# wiPOWER.net
KiCad netlist of a schematic drawn in EAGLE
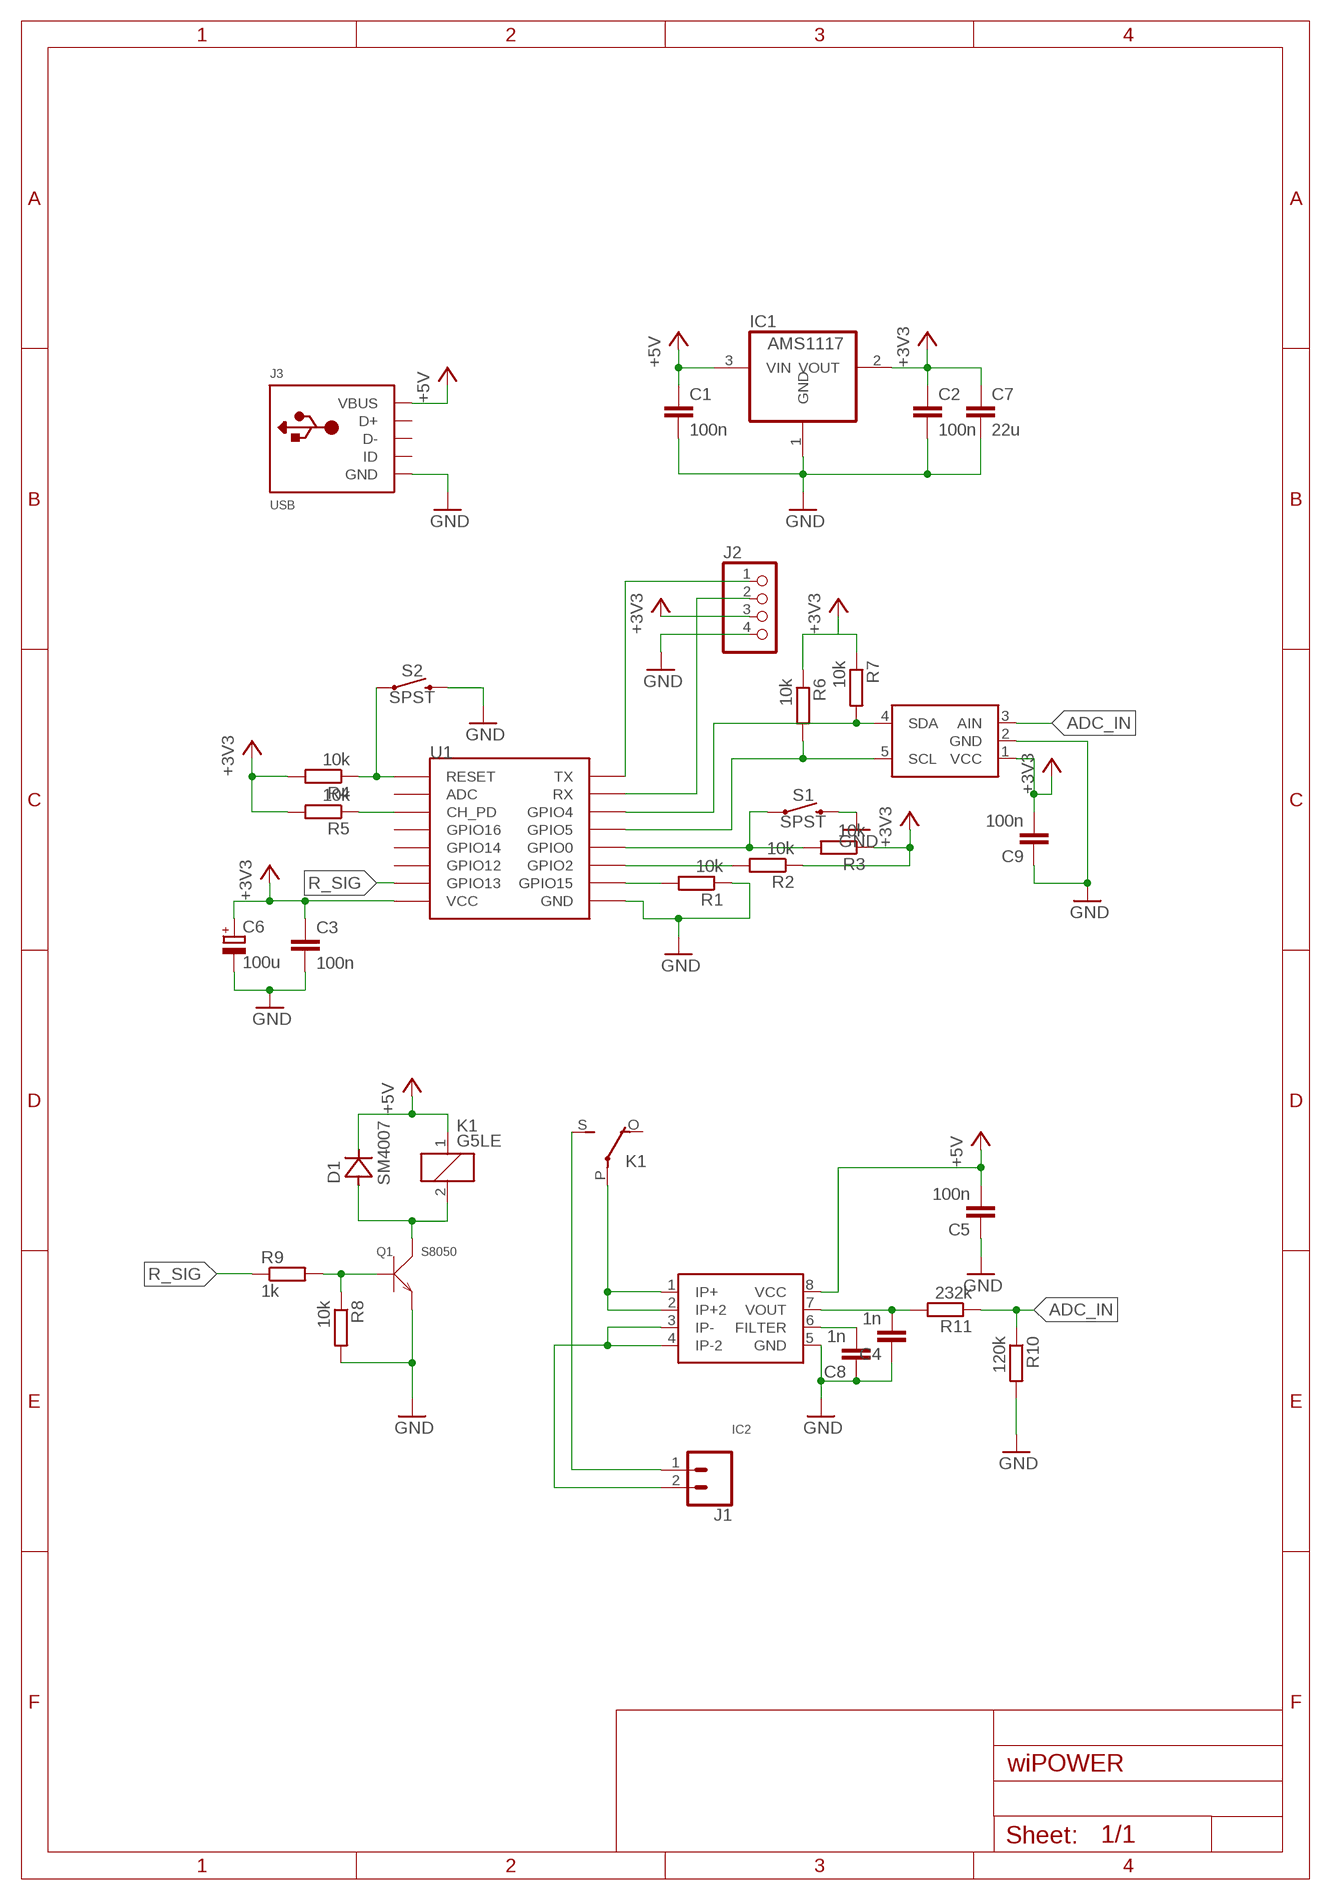
[diagram p0: schematic, sheet 1]

(export (version "E")
  (design (tool "Eeschema 10.0.6"))
  (components
    (comp (ref "C1")
      (value "100n")
      (footprint "eagle-import:C0603")
      (libsource (lib "eagle-import") (part "C-EUC0603"))
    )
    (comp (ref "C2")
      (value "100n")
      (footprint "eagle-import:C0603")
      (libsource (lib "eagle-import") (part "C-EUC0603"))
    )
    (comp (ref "C3")
      (value "100n")
      (footprint "eagle-import:C0603")
      (libsource (lib "eagle-import") (part "C-EUC0603"))
    )
    (comp (ref "C4")
      (value "1n")
      (footprint "eagle-import:C0603")
      (libsource (lib "eagle-import") (part "C-EUC0603"))
    )
    (comp (ref "C5")
      (value "100n")
      (footprint "eagle-import:C0603")
      (libsource (lib "eagle-import") (part "C-EUC0603"))
    )
    (comp (ref "C6")
      (value "100u")
      (footprint "eagle-import:B_3528-21R")
      (libsource (lib "eagle-import") (part "CPOL-EUB/3528-21R"))
    )
    (comp (ref "C7")
      (value "22u")
      (footprint "eagle-import:C0603")
      (libsource (lib "eagle-import") (part "C-EUC0603"))
    )
    (comp (ref "C8")
      (value "1n")
      (footprint "eagle-import:C0603")
      (libsource (lib "eagle-import") (part "C-EUC0603"))
    )
    (comp (ref "C9")
      (value "100n")
      (footprint "eagle-import:C0603")
      (libsource (lib "eagle-import") (part "C-EUC0603"))
    )
    (comp (ref "D1")
      (value "SM4007")
      (footprint "eagle-import:DIODE_SOD123")
      (libsource (lib "eagle-import") (part "SM4007PL"))
    )
    (comp (ref "IC1")
      (value "AMS1117")
      (footprint "eagle-import:SOT223")
      (fields (field (name "MPN") "REG1117"))
      (libsource (lib "eagle-import") (part "REG1117"))
    )
    (comp (ref "IC2")
      (value "ACS724")
      (footprint "eagle-import:SOIC8")
      (libsource (lib "eagle-import") (part "ACS724"))
    )
    (comp (ref "J1")
      (value "CONN_025MM")
      (footprint "eagle-import:SCREWTERMINAL-5MM-2")
      (libsource (lib "eagle-import") (part "CONN_025MM"))
    )
    (comp (ref "J2")
      (value "PINHD-1X4")
      (footprint "eagle-import:1X04")
      (libsource (lib "eagle-import") (part "PINHD-1X4"))
    )
    (comp (ref "J3")
      (value "USB")
      (footprint "eagle-import:MIC-USB")
      (libsource (lib "eagle-import") (part "USB-MICRO"))
    )
    (comp (ref "K1")
      (value "G5LE")
      (footprint "eagle-import:G5LE")
      (libsource (lib "eagle-import") (part "G5LE"))
    )
    (comp (ref "Q1")
      (value "S8050")
      (footprint "eagle-import:SOT-23")
      (libsource (lib "eagle-import") (part "SMD-TRANSISTORS-NPN-25V-500MW-S8050(SOT-23)"))
    )
    (comp (ref "R1")
      (value "10k")
      (footprint "eagle-import:R0603")
      (libsource (lib "eagle-import") (part "R-EU_R0603"))
    )
    (comp (ref "R2")
      (value "10k")
      (footprint "eagle-import:R0603")
      (libsource (lib "eagle-import") (part "R-EU_R0603"))
    )
    (comp (ref "R3")
      (value "10k")
      (footprint "eagle-import:R0603")
      (libsource (lib "eagle-import") (part "R-EU_R0603"))
    )
    (comp (ref "R4")
      (value "10k")
      (footprint "eagle-import:R0603")
      (libsource (lib "eagle-import") (part "R-EU_R0603"))
    )
    (comp (ref "R5")
      (value "10k")
      (footprint "eagle-import:R0603")
      (libsource (lib "eagle-import") (part "R-EU_R0603"))
    )
    (comp (ref "R6")
      (value "10k")
      (footprint "eagle-import:R0603")
      (libsource (lib "eagle-import") (part "R-EU_R0603"))
    )
    (comp (ref "R7")
      (value "10k")
      (footprint "eagle-import:R0603")
      (libsource (lib "eagle-import") (part "R-EU_R0603"))
    )
    (comp (ref "R8")
      (value "10k")
      (footprint "eagle-import:R0603")
      (libsource (lib "eagle-import") (part "R-EU_R0603"))
    )
    (comp (ref "R9")
      (value "1k")
      (footprint "eagle-import:R0603")
      (libsource (lib "eagle-import") (part "R-EU_R0603"))
    )
    (comp (ref "R10")
      (value "120k")
      (footprint "eagle-import:R0603")
      (libsource (lib "eagle-import") (part "R-EU_R0603"))
    )
    (comp (ref "R11")
      (value "232k")
      (footprint "eagle-import:R0603")
      (libsource (lib "eagle-import") (part "R-EU_R0603"))
    )
    (comp (ref "S1")
      (value "SPST")
      (footprint "eagle-import:TACTILE_SWITCH_SMD_6.0X3.5MM")
      (libsource (lib "eagle-import") (part "MOMENTARY-SWITCH-SPST-SMD-6.0X3.5MM"))
    )
    (comp (ref "S2")
      (value "SPST")
      (footprint "eagle-import:TACTILE_SWITCH_SMD_6.0X3.5MM")
      (libsource (lib "eagle-import") (part "MOMENTARY-SWITCH-SPST-SMD-6.0X3.5MM"))
    )
    (comp (ref "U$1")
      (value "MCP3221SOT23-5")
      (footprint "eagle-import:GHI-IC_SOT23-5(MICROCHIP)")
      (libsource (lib "eagle-import") (part "MCP3221SOT23-5"))
    )
    (comp (ref "U1")
      (value "ESP12SMD")
      (footprint "eagle-import:ESP12-SMD")
      (libsource (lib "eagle-import") (part "ESP12SMD"))
    )
  )
  (nets
    (net (code "1") (name "+3V3") (class "Default")
      (node (ref "C2") (pin "1") (pinfunction "1_1") (pintype "passive"))
      (node (ref "C3") (pin "1") (pinfunction "1_1") (pintype "passive"))
      (node (ref "C6") (pin "+") (pinfunction "+_+") (pintype "passive"))
      (node (ref "C7") (pin "1") (pinfunction "1_1") (pintype "passive"))
      (node (ref "C9") (pin "2") (pinfunction "2_2") (pintype "passive"))
      (node (ref "IC1") (pin "2") (pinfunction "VOUT_2") (pintype "output"))
      (node (ref "J2") (pin "3") (pinfunction "3_3") (pintype "passive"))
      (node (ref "R2") (pin "1") (pinfunction "1_1") (pintype "passive"))
      (node (ref "R3") (pin "1") (pinfunction "1_1") (pintype "passive"))
      (node (ref "R4") (pin "2") (pinfunction "2_2") (pintype "passive"))
      (node (ref "R5") (pin "2") (pinfunction "2_2") (pintype "passive"))
      (node (ref "R6") (pin "1") (pinfunction "1_1") (pintype "passive"))
      (node (ref "R7") (pin "1") (pinfunction "1_1") (pintype "passive"))
      (node (ref "U$1") (pin "1") (pinfunction "VCC_1") (pintype "bidirectional"))
      (node (ref "U1") (pin "VCC") (pinfunction "VCC_VCC") (pintype "bidirectional"))
    )
    (net (code "2") (name "+5V") (class "Default")
      (node (ref "C1") (pin "1") (pinfunction "1_1") (pintype "passive"))
      (node (ref "C5") (pin "2") (pinfunction "2_2") (pintype "passive"))
      (node (ref "D1") (pin "C") (pinfunction "C_C") (pintype "passive"))
      (node (ref "IC1") (pin "3") (pinfunction "VIN_3") (pintype "input"))
      (node (ref "IC2") (pin "8") (pinfunction "VCC_8") (pintype "power_in"))
      (node (ref "J3") (pin "P$5") (pinfunction "VBUS_P$5") (pintype "power_in"))
      (node (ref "K1") (pin "1") (pinfunction "1_1") (pintype "passive"))
    )
    (net (code "3") (name "ADC_IN") (class "Default")
      (node (ref "R10") (pin "1") (pinfunction "1_1") (pintype "passive"))
      (node (ref "R11") (pin "1") (pinfunction "1_1") (pintype "passive"))
      (node (ref "U$1") (pin "3") (pinfunction "AIN_3") (pintype "bidirectional"))
    )
    (net (code "4") (name "GND") (class "Default")
      (node (ref "C1") (pin "2") (pinfunction "2_2") (pintype "passive"))
      (node (ref "C2") (pin "2") (pinfunction "2_2") (pintype "passive"))
      (node (ref "C3") (pin "2") (pinfunction "2_2") (pintype "passive"))
      (node (ref "C4") (pin "1") (pinfunction "1_1") (pintype "passive"))
      (node (ref "C5") (pin "1") (pinfunction "1_1") (pintype "passive"))
      (node (ref "C6") (pin "-") (pinfunction "-_-") (pintype "passive"))
      (node (ref "C7") (pin "2") (pinfunction "2_2") (pintype "passive"))
      (node (ref "C8") (pin "1") (pinfunction "1_1") (pintype "passive"))
      (node (ref "C9") (pin "1") (pinfunction "1_1") (pintype "passive"))
      (node (ref "IC1") (pin "1") (pinfunction "GND_1") (pintype "power_in"))
      (node (ref "IC2") (pin "5") (pinfunction "GND_5") (pintype "power_in"))
      (node (ref "J2") (pin "4") (pinfunction "4_4") (pintype "passive"))
      (node (ref "J3") (pin "P$2") (pinfunction "GND_P$2") (pintype "power_in"))
      (node (ref "Q1") (pin "2") (pinfunction "E_2") (pintype "passive"))
      (node (ref "R1") (pin "1") (pinfunction "1_1") (pintype "passive"))
      (node (ref "R10") (pin "2") (pinfunction "2_2") (pintype "passive"))
      (node (ref "R8") (pin "2") (pinfunction "2_2") (pintype "passive"))
      (node (ref "S1") (pin "2") (pinfunction "2_2") (pintype "passive"))
      (node (ref "S2") (pin "2") (pinfunction "2_2") (pintype "passive"))
      (node (ref "U$1") (pin "2") (pinfunction "GND_2") (pintype "bidirectional"))
      (node (ref "U1") (pin "GND") (pinfunction "GND_GND") (pintype "bidirectional"))
    )
    (net (code "5") (name "Net-(IC2-FILTER)") (class "Default")
      (node (ref "C8") (pin "2") (pinfunction "2_2") (pintype "passive"))
      (node (ref "IC2") (pin "6") (pinfunction "FILTER_6") (pintype "bidirectional"))
    )
    (net (code "6") (name "Net-(IC2-IP+)") (class "Default")
      (node (ref "IC2") (pin "1") (pinfunction "IP+_1") (pintype "bidirectional"))
      (node (ref "IC2") (pin "2") (pinfunction "IP+2_2") (pintype "bidirectional"))
      (node (ref "K1") (pin "P") (pinfunction "P_P") (pintype "passive"))
    )
    (net (code "7") (name "Net-(IC2-IP-)") (class "Default")
      (node (ref "IC2") (pin "3") (pinfunction "IP-_3") (pintype "bidirectional"))
      (node (ref "IC2") (pin "4") (pinfunction "IP-2_4") (pintype "bidirectional"))
      (node (ref "J1") (pin "2") (pinfunction "2_2") (pintype "passive"))
    )
    (net (code "8") (name "Net-(IC2-VOUT)") (class "Default")
      (node (ref "C4") (pin "2") (pinfunction "2_2") (pintype "passive"))
      (node (ref "IC2") (pin "7") (pinfunction "VOUT_7") (pintype "bidirectional"))
      (node (ref "R11") (pin "2") (pinfunction "2_2") (pintype "passive"))
    )
    (net (code "9") (name "Net-(J1-Pad1)") (class "Default")
      (node (ref "J1") (pin "1") (pinfunction "1_1") (pintype "passive"))
      (node (ref "K1") (pin "S") (pinfunction "S_S") (pintype "passive"))
    )
    (net (code "10") (name "Net-(Q1-B)") (class "Default")
      (node (ref "Q1") (pin "1") (pinfunction "B_1") (pintype "passive"))
      (node (ref "R8") (pin "1") (pinfunction "1_1") (pintype "passive"))
      (node (ref "R9") (pin "2") (pinfunction "2_2") (pintype "passive"))
    )
    (net (code "11") (name "Net-(Q1-C)") (class "Default")
      (node (ref "D1") (pin "A") (pinfunction "A_A") (pintype "passive"))
      (node (ref "K1") (pin "2") (pinfunction "2_2") (pintype "passive"))
      (node (ref "Q1") (pin "3") (pinfunction "C_3") (pintype "passive"))
    )
    (net (code "12") (name "Net-(R1-Pad2)") (class "Default")
      (node (ref "R1") (pin "2") (pinfunction "2_2") (pintype "passive"))
      (node (ref "U1") (pin "GPIO15") (pinfunction "GPIO15_GPIO15") (pintype "bidirectional"))
    )
    (net (code "13") (name "Net-(R2-Pad2)") (class "Default")
      (node (ref "R2") (pin "2") (pinfunction "2_2") (pintype "passive"))
      (node (ref "U1") (pin "GPIO2") (pinfunction "GPIO2_GPIO2") (pintype "bidirectional"))
    )
    (net (code "14") (name "Net-(R3-Pad2)") (class "Default")
      (node (ref "R3") (pin "2") (pinfunction "2_2") (pintype "passive"))
      (node (ref "S1") (pin "1") (pinfunction "1_1") (pintype "passive"))
      (node (ref "U1") (pin "GPIO0") (pinfunction "GPIO0_GPIO0") (pintype "bidirectional"))
    )
    (net (code "15") (name "Net-(R4-Pad1)") (class "Default")
      (node (ref "R4") (pin "1") (pinfunction "1_1") (pintype "passive"))
      (node (ref "S2") (pin "1") (pinfunction "1_1") (pintype "passive"))
      (node (ref "U1") (pin "RESET") (pinfunction "RESET_RESET") (pintype "bidirectional"))
    )
    (net (code "16") (name "Net-(R5-Pad1)") (class "Default")
      (node (ref "R5") (pin "1") (pinfunction "1_1") (pintype "passive"))
      (node (ref "U1") (pin "CH_PD") (pinfunction "CH_PD_CH_PD") (pintype "bidirectional"))
    )
    (net (code "17") (name "Net-(U$1-SCL)") (class "Default")
      (node (ref "R6") (pin "2") (pinfunction "2_2") (pintype "passive"))
      (node (ref "U$1") (pin "5") (pinfunction "SCL_5") (pintype "bidirectional"))
      (node (ref "U1") (pin "GPIO5") (pinfunction "GPIO5_GPIO5") (pintype "bidirectional"))
    )
    (net (code "18") (name "Net-(U$1-SDA)") (class "Default")
      (node (ref "R7") (pin "2") (pinfunction "2_2") (pintype "passive"))
      (node (ref "U$1") (pin "4") (pinfunction "SDA_4") (pintype "bidirectional"))
      (node (ref "U1") (pin "GPIO4") (pinfunction "GPIO4_GPIO4") (pintype "bidirectional"))
    )
    (net (code "19") (name "Net-(U1-RX)") (class "Default")
      (node (ref "J2") (pin "2") (pinfunction "2_2") (pintype "passive"))
      (node (ref "U1") (pin "RXD0") (pinfunction "RX_RXD0") (pintype "bidirectional"))
    )
    (net (code "20") (name "Net-(U1-TX)") (class "Default")
      (node (ref "J2") (pin "1") (pinfunction "1_1") (pintype "passive"))
      (node (ref "U1") (pin "TXD0") (pinfunction "TX_TXD0") (pintype "bidirectional"))
    )
    (net (code "21") (name "R_SIG") (class "Default")
      (node (ref "R9") (pin "1") (pinfunction "1_1") (pintype "passive"))
      (node (ref "U1") (pin "GPIO13") (pinfunction "GPIO13_GPIO13") (pintype "bidirectional"))
    )
    (net (code "22") (name "unconnected-(J3-D+-PadP$3)") (class "Default")
      (node (ref "J3") (pin "P$3") (pinfunction "D+_P$3") (pintype "bidirectional"))
    )
    (net (code "23") (name "unconnected-(J3-D--PadP$4)") (class "Default")
      (node (ref "J3") (pin "P$4") (pinfunction "D-_P$4") (pintype "bidirectional"))
    )
    (net (code "24") (name "unconnected-(J3-ID-PadP$1)") (class "Default")
      (node (ref "J3") (pin "P$1") (pinfunction "ID_P$1") (pintype "bidirectional"))
    )
    (net (code "25") (name "unconnected-(K1-PadO)") (class "Default")
      (node (ref "K1") (pin "O") (pinfunction "O_O") (pintype "passive"))
    )
    (net (code "26") (name "unconnected-(U1-PadADC)") (class "Default")
      (node (ref "U1") (pin "ADC") (pinfunction "ADC_ADC") (pintype "bidirectional"))
    )
    (net (code "27") (name "unconnected-(U1-PadGPIO12)") (class "Default")
      (node (ref "U1") (pin "GPIO12") (pinfunction "GPIO12_GPIO12") (pintype "bidirectional"))
    )
    (net (code "28") (name "unconnected-(U1-PadGPIO14)") (class "Default")
      (node (ref "U1") (pin "GPIO14") (pinfunction "GPIO14_GPIO14") (pintype "bidirectional"))
    )
    (net (code "29") (name "unconnected-(U1-PadGPIO16)") (class "Default")
      (node (ref "U1") (pin "GPIO16") (pinfunction "GPIO16_GPIO16") (pintype "bidirectional"))
    )
  )
)
